# ICEBoard_rev1_1.net
KiCad netlist of a schematic drawn in Altium Designer
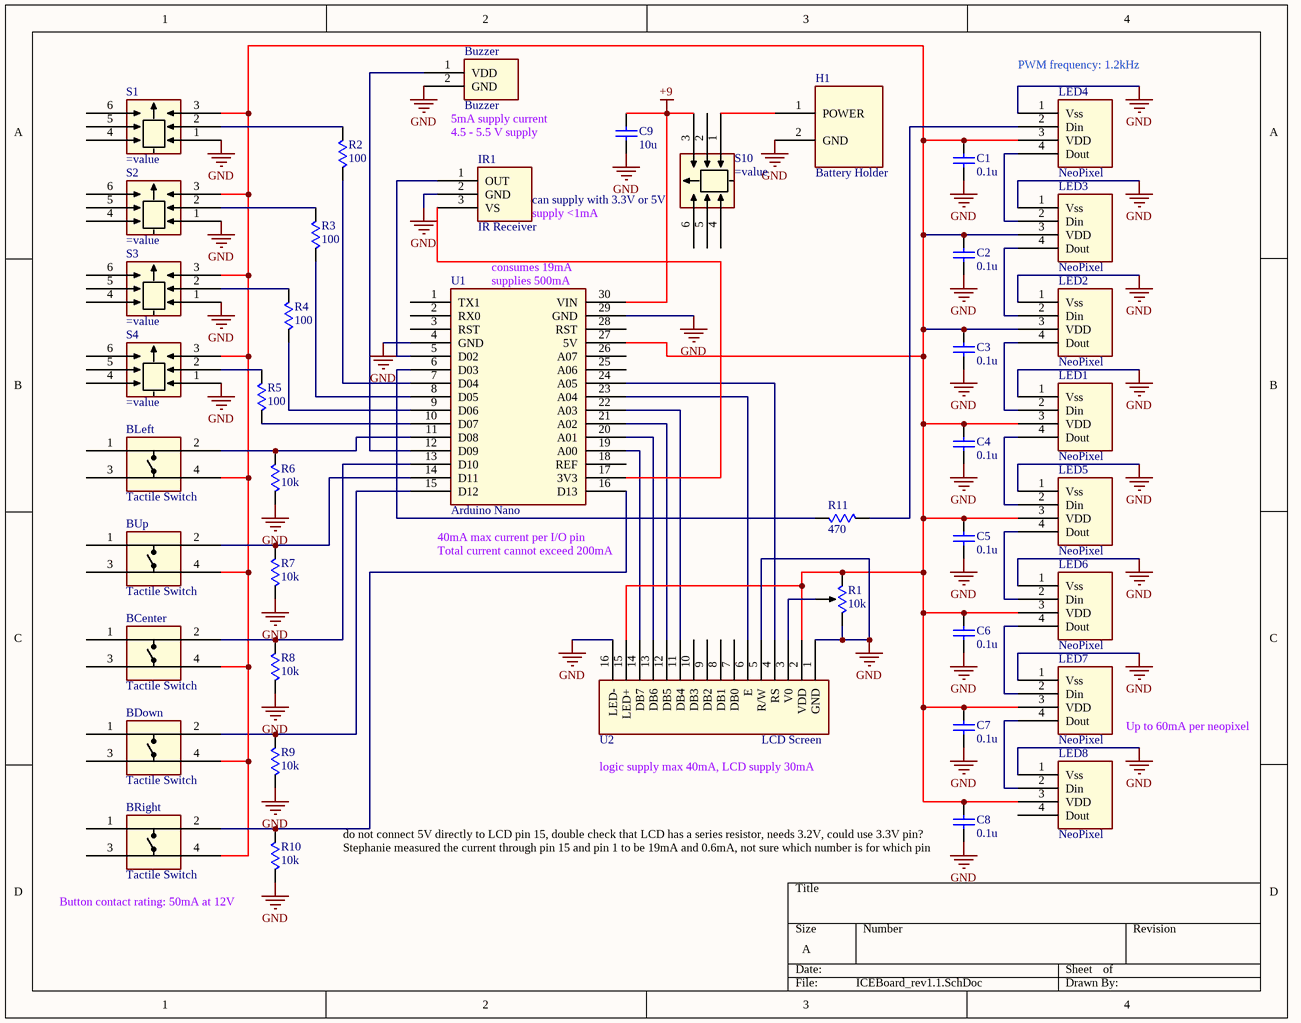
[diagram p0: ICEBoard_rev1.1.SchDoc]

(export (version "E")
  (design (tool "Eeschema 10.0.6"))
  (components
    (comp (ref "BCenter")
      (value "Tactile Switch")
      (footprint "PTS645")
      (libsource (lib "PTS645") (part "PTS645"))
    )
    (comp (ref "BDown")
      (value "Tactile Switch")
      (footprint "PTS645")
      (libsource (lib "PTS645") (part "PTS645"))
    )
    (comp (ref "BLeft")
      (value "Tactile Switch")
      (footprint "PTS645")
      (libsource (lib "PTS645") (part "PTS645"))
    )
    (comp (ref "BRight")
      (value "Tactile Switch")
      (footprint "PTS645")
      (libsource (lib "PTS645") (part "PTS645"))
    )
    (comp (ref "BUp")
      (value "Tactile Switch")
      (footprint "PTS645")
      (libsource (lib "PTS645") (part "PTS645"))
    )
    (comp (ref "Buzzer")
      (value "Buzzer")
      (footprint "TP124005")
      (libsource (lib "TP124005") (part "TP124005"))
    )
    (comp (ref "C1") (value "0.1u") (footprint "Capacitor") (libsource (lib "Capacitor") (part "Capacitor")))
    (comp (ref "C2") (value "0.1u") (footprint "Capacitor") (libsource (lib "Capacitor") (part "Capacitor")))
    (comp (ref "C3") (value "0.1u") (footprint "Capacitor") (libsource (lib "Capacitor") (part "Capacitor")))
    (comp (ref "C4") (value "0.1u") (footprint "Capacitor") (libsource (lib "Capacitor") (part "Capacitor")))
    (comp (ref "C5") (value "0.1u") (footprint "Capacitor") (libsource (lib "Capacitor") (part "Capacitor")))
    (comp (ref "C6") (value "0.1u") (footprint "Capacitor") (libsource (lib "Capacitor") (part "Capacitor")))
    (comp (ref "C7") (value "0.1u") (footprint "Capacitor") (libsource (lib "Capacitor") (part "Capacitor")))
    (comp (ref "C8") (value "0.1u") (footprint "Capacitor") (libsource (lib "Capacitor") (part "Capacitor")))
    (comp (ref "C9")
      (value "10u")
      (footprint "PCBComponent_1")
      (libsource (lib "Capacitor") (part "Capacitor"))
    )
    (comp (ref "H1") (value "Battery Holder") (footprint "BH9VPC") (libsource (lib "BH9VPC") (part "BH9VPC")))
    (comp (ref "IR1")
      (value "IR Receiver")
      (footprint "TSOP382")
      (libsource (lib "TSOP382") (part "TSOP382"))
    )
    (comp (ref "LED1")
      (value "NeoPixel")
      (footprint "NeoPixel")
      (libsource (lib "NeoPixel") (part "NeoPixel"))
    )
    (comp (ref "LED2")
      (value "NeoPixel")
      (footprint "NeoPixel")
      (libsource (lib "NeoPixel") (part "NeoPixel"))
    )
    (comp (ref "LED3")
      (value "NeoPixel")
      (footprint "NeoPixel")
      (libsource (lib "NeoPixel") (part "NeoPixel"))
    )
    (comp (ref "LED4")
      (value "NeoPixel")
      (footprint "NeoPixel")
      (libsource (lib "NeoPixel") (part "NeoPixel"))
    )
    (comp (ref "LED5")
      (value "NeoPixel")
      (footprint "NeoPixel")
      (libsource (lib "NeoPixel") (part "NeoPixel"))
    )
    (comp (ref "LED6")
      (value "NeoPixel")
      (footprint "NeoPixel")
      (libsource (lib "NeoPixel") (part "NeoPixel"))
    )
    (comp (ref "LED7")
      (value "NeoPixel")
      (footprint "NeoPixel")
      (libsource (lib "NeoPixel") (part "NeoPixel"))
    )
    (comp (ref "LED8")
      (value "NeoPixel")
      (footprint "NeoPixel")
      (libsource (lib "NeoPixel") (part "NeoPixel"))
    )
    (comp (ref "R1")
      (value "10k")
      (footprint "TC33X")
      (libsource (lib "Resistor - Variable") (part "Resistor - Variable"))
    )
    (comp (ref "R2") (value "100") (footprint "Resistor1608") (libsource (lib "Resistor") (part "Resistor")))
    (comp (ref "R3") (value "100") (footprint "Resistor1608") (libsource (lib "Resistor") (part "Resistor")))
    (comp (ref "R4") (value "100") (footprint "Resistor1608") (libsource (lib "Resistor") (part "Resistor")))
    (comp (ref "R5") (value "100") (footprint "Resistor1608") (libsource (lib "Resistor") (part "Resistor")))
    (comp (ref "R6") (value "10k") (footprint "Resistor1608") (libsource (lib "Resistor") (part "Resistor")))
    (comp (ref "R7") (value "10k") (footprint "Resistor1608") (libsource (lib "Resistor") (part "Resistor")))
    (comp (ref "R8") (value "10k") (footprint "Resistor1608") (libsource (lib "Resistor") (part "Resistor")))
    (comp (ref "R9") (value "10k") (footprint "Resistor1608") (libsource (lib "Resistor") (part "Resistor")))
    (comp (ref "R10") (value "10k") (footprint "Resistor1608") (libsource (lib "Resistor") (part "Resistor")))
    (comp (ref "R11") (value "470") (footprint "Resistor1608") (libsource (lib "Resistor") (part "Resistor")))
    (comp (ref "S1") (value "~") (footprint "MHSS1104") (libsource (lib "MHSS1104") (part "MHSS1104")))
    (comp (ref "S2") (value "~") (footprint "MHSS1104") (libsource (lib "MHSS1104") (part "MHSS1104")))
    (comp (ref "S3") (value "~") (footprint "MHSS1104") (libsource (lib "MHSS1104") (part "MHSS1104")))
    (comp (ref "S4") (value "~") (footprint "MHSS1104") (libsource (lib "MHSS1104") (part "MHSS1104")))
    (comp (ref "S10") (value "~") (footprint "MHSS1104") (libsource (lib "") (part "MHSS1104_1")))
    (comp (ref "U1")
      (value "Arduino Nano")
      (footprint "ArduinoNano")
      (libsource (lib "ArduinoNano") (part "ArduinoNano"))
    )
    (comp (ref "U2")
      (value "LCD Screen")
      (footprint "TC1602A-01T")
      (libsource (lib "TC1602A-01T") (part "TC1602A-01T"))
    )
  )
  (nets
    (net (code "1") (name "+9") (class "Default")
      (node (ref "C9") (pin "1") (pinfunction "1_1") (pintype "passive"))
      (node (ref "S10") (pin "3") (pintype "passive"))
      (node (ref "U1") (pin "30") (pinfunction "VIN_30") (pintype "passive"))
    )
    (net (code "2") (name "GND") (class "Default")
      (node (ref "Buzzer") (pin "2") (pinfunction "GND_2") (pintype "passive"))
      (node (ref "C1") (pin "2") (pinfunction "2_2") (pintype "passive"))
      (node (ref "C2") (pin "2") (pinfunction "2_2") (pintype "passive"))
      (node (ref "C3") (pin "2") (pinfunction "2_2") (pintype "passive"))
      (node (ref "C4") (pin "2") (pinfunction "2_2") (pintype "passive"))
      (node (ref "C5") (pin "2") (pinfunction "2_2") (pintype "passive"))
      (node (ref "C6") (pin "2") (pinfunction "2_2") (pintype "passive"))
      (node (ref "C7") (pin "2") (pinfunction "2_2") (pintype "passive"))
      (node (ref "C8") (pin "2") (pinfunction "2_2") (pintype "passive"))
      (node (ref "C9") (pin "2") (pinfunction "2_2") (pintype "passive"))
      (node (ref "H1") (pin "2") (pinfunction "GND_2") (pintype "passive"))
      (node (ref "IR1") (pin "2") (pinfunction "GND_2") (pintype "passive"))
      (node (ref "LED1") (pin "1") (pinfunction "Vss_1") (pintype "passive"))
      (node (ref "LED2") (pin "1") (pinfunction "Vss_1") (pintype "passive"))
      (node (ref "LED3") (pin "1") (pinfunction "Vss_1") (pintype "passive"))
      (node (ref "LED4") (pin "1") (pinfunction "Vss_1") (pintype "passive"))
      (node (ref "LED5") (pin "1") (pinfunction "Vss_1") (pintype "passive"))
      (node (ref "LED6") (pin "1") (pinfunction "Vss_1") (pintype "passive"))
      (node (ref "LED7") (pin "1") (pinfunction "Vss_1") (pintype "passive"))
      (node (ref "LED8") (pin "1") (pinfunction "Vss_1") (pintype "passive"))
      (node (ref "R1") (pin "1") (pinfunction "1_1") (pintype "passive"))
      (node (ref "R10") (pin "1") (pinfunction "1_1") (pintype "passive"))
      (node (ref "R6") (pin "1") (pinfunction "1_1") (pintype "passive"))
      (node (ref "R7") (pin "1") (pinfunction "1_1") (pintype "passive"))
      (node (ref "R8") (pin "1") (pinfunction "1_1") (pintype "passive"))
      (node (ref "R9") (pin "1") (pinfunction "1_1") (pintype "passive"))
      (node (ref "S1") (pin "1") (pintype "passive"))
      (node (ref "S2") (pin "1") (pintype "passive"))
      (node (ref "S3") (pin "1") (pintype "passive"))
      (node (ref "S4") (pin "1") (pintype "passive"))
      (node (ref "U1") (pin "29") (pinfunction "GND_29") (pintype "passive"))
      (node (ref "U1") (pin "4") (pinfunction "GND_4") (pintype "passive"))
      (node (ref "U2") (pin "1") (pinfunction "GND_1") (pintype "passive"))
      (node (ref "U2") (pin "16") (pinfunction "LED-_16") (pintype "passive"))
      (node (ref "U2") (pin "5") (pinfunction "R/W_5") (pintype "passive"))
    )
    (net (code "3") (name "Net-(Buzzer-VDD)") (class "Default")
      (node (ref "Buzzer") (pin "1") (pinfunction "VDD_1") (pintype "passive"))
      (node (ref "U1") (pin "12") (pinfunction "D09_12") (pintype "passive"))
    )
    (net (code "4") (name "Net-(H1-POWER)") (class "Default")
      (node (ref "H1") (pin "1") (pinfunction "POWER_1") (pintype "passive"))
      (node (ref "S10") (pin "1") (pintype "passive"))
    )
    (net (code "5") (name "Net-(IR1-OUT)") (class "Default")
      (node (ref "IR1") (pin "1") (pinfunction "OUT_1") (pintype "passive"))
      (node (ref "U1") (pin "5") (pinfunction "D02_5") (pintype "passive"))
    )
    (net (code "6") (name "Net-(IR1-VS)") (class "Default")
      (node (ref "IR1") (pin "3") (pinfunction "VS_3") (pintype "passive"))
      (node (ref "U1") (pin "17") (pinfunction "3V3_17") (pintype "passive"))
    )
    (net (code "7") (name "Net-(LED1-Din)") (class "Default")
      (node (ref "LED1") (pin "2") (pinfunction "Din_2") (pintype "passive"))
      (node (ref "LED2") (pin "4") (pinfunction "Dout_4") (pintype "passive"))
    )
    (net (code "8") (name "Net-(LED1-Dout)") (class "Default")
      (node (ref "LED1") (pin "4") (pinfunction "Dout_4") (pintype "passive"))
      (node (ref "LED5") (pin "2") (pinfunction "Din_2") (pintype "passive"))
    )
    (net (code "9") (name "Net-(LED1-VDD)") (class "Default")
      (node (ref "BCenter") (pin "4") (pintype "passive"))
      (node (ref "BDown") (pin "4") (pintype "passive"))
      (node (ref "BLeft") (pin "4") (pintype "passive"))
      (node (ref "BRight") (pin "4") (pintype "passive"))
      (node (ref "BUp") (pin "4") (pintype "passive"))
      (node (ref "C1") (pin "1") (pinfunction "1_1") (pintype "passive"))
      (node (ref "C2") (pin "1") (pinfunction "1_1") (pintype "passive"))
      (node (ref "C3") (pin "1") (pinfunction "1_1") (pintype "passive"))
      (node (ref "C4") (pin "1") (pinfunction "1_1") (pintype "passive"))
      (node (ref "C5") (pin "1") (pinfunction "1_1") (pintype "passive"))
      (node (ref "C6") (pin "1") (pinfunction "1_1") (pintype "passive"))
      (node (ref "C7") (pin "1") (pinfunction "1_1") (pintype "passive"))
      (node (ref "C8") (pin "1") (pinfunction "1_1") (pintype "passive"))
      (node (ref "LED1") (pin "3") (pinfunction "VDD_3") (pintype "passive"))
      (node (ref "LED2") (pin "3") (pinfunction "VDD_3") (pintype "passive"))
      (node (ref "LED3") (pin "3") (pinfunction "VDD_3") (pintype "passive"))
      (node (ref "LED4") (pin "3") (pinfunction "VDD_3") (pintype "passive"))
      (node (ref "LED5") (pin "3") (pinfunction "VDD_3") (pintype "passive"))
      (node (ref "LED6") (pin "3") (pinfunction "VDD_3") (pintype "passive"))
      (node (ref "LED7") (pin "3") (pinfunction "VDD_3") (pintype "passive"))
      (node (ref "LED8") (pin "3") (pinfunction "VDD_3") (pintype "passive"))
      (node (ref "R1") (pin "3") (pinfunction "3_3") (pintype "passive"))
      (node (ref "S1") (pin "3") (pintype "passive"))
      (node (ref "S2") (pin "3") (pintype "passive"))
      (node (ref "S3") (pin "3") (pintype "passive"))
      (node (ref "S4") (pin "3") (pintype "passive"))
      (node (ref "U1") (pin "27") (pinfunction "5V_27") (pintype "passive"))
      (node (ref "U2") (pin "15") (pinfunction "LED+_15") (pintype "passive"))
      (node (ref "U2") (pin "2") (pinfunction "VDD_2") (pintype "passive"))
    )
    (net (code "10") (name "Net-(LED2-Din)") (class "Default")
      (node (ref "LED2") (pin "2") (pinfunction "Din_2") (pintype "passive"))
      (node (ref "LED3") (pin "4") (pinfunction "Dout_4") (pintype "passive"))
    )
    (net (code "11") (name "Net-(LED3-Din)") (class "Default")
      (node (ref "LED3") (pin "2") (pinfunction "Din_2") (pintype "passive"))
      (node (ref "LED4") (pin "4") (pinfunction "Dout_4") (pintype "passive"))
    )
    (net (code "12") (name "Net-(LED4-Din)") (class "Default")
      (node (ref "LED4") (pin "2") (pinfunction "Din_2") (pintype "passive"))
      (node (ref "R11") (pin "2") (pinfunction "2_2") (pintype "passive"))
    )
    (net (code "13") (name "Net-(LED5-Dout)") (class "Default")
      (node (ref "LED5") (pin "4") (pinfunction "Dout_4") (pintype "passive"))
      (node (ref "LED6") (pin "2") (pinfunction "Din_2") (pintype "passive"))
    )
    (net (code "14") (name "Net-(LED6-Dout)") (class "Default")
      (node (ref "LED6") (pin "4") (pinfunction "Dout_4") (pintype "passive"))
      (node (ref "LED7") (pin "2") (pinfunction "Din_2") (pintype "passive"))
    )
    (net (code "15") (name "Net-(LED7-Dout)") (class "Default")
      (node (ref "LED7") (pin "4") (pinfunction "Dout_4") (pintype "passive"))
      (node (ref "LED8") (pin "2") (pinfunction "Din_2") (pintype "passive"))
    )
    (net (code "16") (name "Net-(R2-Pad2)") (class "Default")
      (node (ref "R2") (pin "2") (pinfunction "2_2") (pintype "passive"))
      (node (ref "S1") (pin "2") (pintype "passive"))
    )
    (net (code "17") (name "Net-(R3-Pad2)") (class "Default")
      (node (ref "R3") (pin "2") (pinfunction "2_2") (pintype "passive"))
      (node (ref "S2") (pin "2") (pintype "passive"))
    )
    (net (code "18") (name "Net-(R4-Pad2)") (class "Default")
      (node (ref "R4") (pin "2") (pinfunction "2_2") (pintype "passive"))
      (node (ref "S3") (pin "2") (pintype "passive"))
    )
    (net (code "19") (name "Net-(R5-Pad2)") (class "Default")
      (node (ref "R5") (pin "2") (pinfunction "2_2") (pintype "passive"))
      (node (ref "S4") (pin "2") (pintype "passive"))
    )
    (net (code "20") (name "Net-(U1-A00)") (class "Default")
      (node (ref "U1") (pin "19") (pinfunction "A00_19") (pintype "passive"))
      (node (ref "U2") (pin "14") (pinfunction "DB7_14") (pintype "passive"))
    )
    (net (code "21") (name "Net-(U1-A01)") (class "Default")
      (node (ref "U1") (pin "20") (pinfunction "A01_20") (pintype "passive"))
      (node (ref "U2") (pin "13") (pinfunction "DB6_13") (pintype "passive"))
    )
    (net (code "22") (name "Net-(U1-A02)") (class "Default")
      (node (ref "U1") (pin "21") (pinfunction "A02_21") (pintype "passive"))
      (node (ref "U2") (pin "12") (pinfunction "DB5_12") (pintype "passive"))
    )
    (net (code "23") (name "Net-(U1-A03)") (class "Default")
      (node (ref "U1") (pin "22") (pinfunction "A03_22") (pintype "passive"))
      (node (ref "U2") (pin "11") (pinfunction "DB4_11") (pintype "passive"))
    )
    (net (code "24") (name "Net-(U1-A04)") (class "Default")
      (node (ref "U1") (pin "23") (pinfunction "A04_23") (pintype "passive"))
      (node (ref "U2") (pin "6") (pinfunction "E_6") (pintype "passive"))
    )
    (net (code "25") (name "Net-(U1-A05)") (class "Default")
      (node (ref "U1") (pin "24") (pinfunction "A05_24") (pintype "passive"))
      (node (ref "U2") (pin "4") (pinfunction "RS_4") (pintype "passive"))
    )
    (net (code "26") (name "Net-(U1-D03)") (class "Default")
      (node (ref "R11") (pin "1") (pinfunction "1_1") (pintype "passive"))
      (node (ref "U1") (pin "6") (pinfunction "D03_6") (pintype "passive"))
    )
    (net (code "27") (name "Net-(U1-D04)") (class "Default")
      (node (ref "R2") (pin "1") (pinfunction "1_1") (pintype "passive"))
      (node (ref "U1") (pin "7") (pinfunction "D04_7") (pintype "passive"))
    )
    (net (code "28") (name "Net-(U1-D05)") (class "Default")
      (node (ref "R3") (pin "1") (pinfunction "1_1") (pintype "passive"))
      (node (ref "U1") (pin "8") (pinfunction "D05_8") (pintype "passive"))
    )
    (net (code "29") (name "Net-(U1-D06)") (class "Default")
      (node (ref "R4") (pin "1") (pinfunction "1_1") (pintype "passive"))
      (node (ref "U1") (pin "9") (pinfunction "D06_9") (pintype "passive"))
    )
    (net (code "30") (name "Net-(U1-D07)") (class "Default")
      (node (ref "R5") (pin "1") (pinfunction "1_1") (pintype "passive"))
      (node (ref "U1") (pin "10") (pinfunction "D07_10") (pintype "passive"))
    )
    (net (code "31") (name "Net-(U1-D08)") (class "Default")
      (node (ref "BLeft") (pin "2") (pintype "passive"))
      (node (ref "R6") (pin "2") (pinfunction "2_2") (pintype "passive"))
      (node (ref "U1") (pin "11") (pinfunction "D08_11") (pintype "passive"))
    )
    (net (code "32") (name "Net-(U1-D10)") (class "Default")
      (node (ref "BCenter") (pin "2") (pintype "passive"))
      (node (ref "R8") (pin "2") (pinfunction "2_2") (pintype "passive"))
      (node (ref "U1") (pin "13") (pinfunction "D10_13") (pintype "passive"))
    )
    (net (code "33") (name "Net-(U1-D11)") (class "Default")
      (node (ref "BUp") (pin "2") (pintype "passive"))
      (node (ref "R7") (pin "2") (pinfunction "2_2") (pintype "passive"))
      (node (ref "U1") (pin "14") (pinfunction "D11_14") (pintype "passive"))
    )
    (net (code "34") (name "Net-(U1-D12)") (class "Default")
      (node (ref "BDown") (pin "2") (pintype "passive"))
      (node (ref "R9") (pin "2") (pinfunction "2_2") (pintype "passive"))
      (node (ref "U1") (pin "15") (pinfunction "D12_15") (pintype "passive"))
    )
    (net (code "35") (name "Net-(U1-D13)") (class "Default")
      (node (ref "BRight") (pin "2") (pintype "passive"))
      (node (ref "R10") (pin "2") (pinfunction "2_2") (pintype "passive"))
      (node (ref "U1") (pin "16") (pinfunction "D13_16") (pintype "passive"))
    )
    (net (code "36") (name "Net-(U2-V0)") (class "Default")
      (node (ref "R1") (pin "2") (pinfunction "2_2") (pintype "passive"))
      (node (ref "U2") (pin "3") (pinfunction "V0_3") (pintype "passive"))
    )
    (net (code "37") (name "unconnected-(BCenter-Pad1)") (class "Default")
      (node (ref "BCenter") (pin "1") (pintype "passive"))
    )
    (net (code "38") (name "unconnected-(BCenter-Pad3)") (class "Default")
      (node (ref "BCenter") (pin "3") (pintype "passive"))
    )
    (net (code "39") (name "unconnected-(BDown-Pad1)") (class "Default")
      (node (ref "BDown") (pin "1") (pintype "passive"))
    )
    (net (code "40") (name "unconnected-(BDown-Pad3)") (class "Default")
      (node (ref "BDown") (pin "3") (pintype "passive"))
    )
    (net (code "41") (name "unconnected-(BLeft-Pad1)") (class "Default")
      (node (ref "BLeft") (pin "1") (pintype "passive"))
    )
    (net (code "42") (name "unconnected-(BLeft-Pad3)") (class "Default")
      (node (ref "BLeft") (pin "3") (pintype "passive"))
    )
    (net (code "43") (name "unconnected-(BRight-Pad1)") (class "Default")
      (node (ref "BRight") (pin "1") (pintype "passive"))
    )
    (net (code "44") (name "unconnected-(BRight-Pad3)") (class "Default")
      (node (ref "BRight") (pin "3") (pintype "passive"))
    )
    (net (code "45") (name "unconnected-(BUp-Pad1)") (class "Default")
      (node (ref "BUp") (pin "1") (pintype "passive"))
    )
    (net (code "46") (name "unconnected-(BUp-Pad3)") (class "Default")
      (node (ref "BUp") (pin "3") (pintype "passive"))
    )
    (net (code "47") (name "unconnected-(LED8-Dout-Pad4)") (class "Default")
      (node (ref "LED8") (pin "4") (pinfunction "Dout_4") (pintype "passive"))
    )
    (net (code "48") (name "unconnected-(S1-Pad4)") (class "Default")
      (node (ref "S1") (pin "4") (pintype "passive"))
    )
    (net (code "49") (name "unconnected-(S1-Pad5)") (class "Default")
      (node (ref "S1") (pin "5") (pintype "passive"))
    )
    (net (code "50") (name "unconnected-(S1-Pad6)") (class "Default")
      (node (ref "S1") (pin "6") (pintype "passive"))
    )
    (net (code "51") (name "unconnected-(S2-Pad4)") (class "Default")
      (node (ref "S2") (pin "4") (pintype "passive"))
    )
    (net (code "52") (name "unconnected-(S2-Pad5)") (class "Default")
      (node (ref "S2") (pin "5") (pintype "passive"))
    )
    (net (code "53") (name "unconnected-(S2-Pad6)") (class "Default")
      (node (ref "S2") (pin "6") (pintype "passive"))
    )
    (net (code "54") (name "unconnected-(S3-Pad4)") (class "Default")
      (node (ref "S3") (pin "4") (pintype "passive"))
    )
    (net (code "55") (name "unconnected-(S3-Pad5)") (class "Default")
      (node (ref "S3") (pin "5") (pintype "passive"))
    )
    (net (code "56") (name "unconnected-(S3-Pad6)") (class "Default")
      (node (ref "S3") (pin "6") (pintype "passive"))
    )
    (net (code "57") (name "unconnected-(S4-Pad4)") (class "Default")
      (node (ref "S4") (pin "4") (pintype "passive"))
    )
    (net (code "58") (name "unconnected-(S4-Pad5)") (class "Default")
      (node (ref "S4") (pin "5") (pintype "passive"))
    )
    (net (code "59") (name "unconnected-(S4-Pad6)") (class "Default")
      (node (ref "S4") (pin "6") (pintype "passive"))
    )
    (net (code "60") (name "unconnected-(S10-Pad2)") (class "Default")
      (node (ref "S10") (pin "2") (pintype "passive"))
    )
    (net (code "61") (name "unconnected-(S10-Pad4)") (class "Default")
      (node (ref "S10") (pin "4") (pintype "passive"))
    )
    (net (code "62") (name "unconnected-(S10-Pad5)") (class "Default")
      (node (ref "S10") (pin "5") (pintype "passive"))
    )
    (net (code "63") (name "unconnected-(S10-Pad6)") (class "Default")
      (node (ref "S10") (pin "6") (pintype "passive"))
    )
    (net (code "64") (name "unconnected-(U1-A06-Pad25)") (class "Default")
      (node (ref "U1") (pin "25") (pinfunction "A06_25") (pintype "passive"))
    )
    (net (code "65") (name "unconnected-(U1-A07-Pad26)") (class "Default")
      (node (ref "U1") (pin "26") (pinfunction "A07_26") (pintype "passive"))
    )
    (net (code "66") (name "unconnected-(U1-REF-Pad18)") (class "Default")
      (node (ref "U1") (pin "18") (pinfunction "REF_18") (pintype "passive"))
    )
    (net (code "67") (name "unconnected-(U1-RST-Pad3)") (class "Default")
      (node (ref "U1") (pin "3") (pinfunction "RST_3") (pintype "passive"))
    )
    (net (code "68") (name "unconnected-(U1-RST-Pad28)") (class "Default")
      (node (ref "U1") (pin "28") (pinfunction "RST_28") (pintype "passive"))
    )
    (net (code "69") (name "unconnected-(U1-RX0-Pad2)") (class "Default")
      (node (ref "U1") (pin "2") (pinfunction "RX0_2") (pintype "passive"))
    )
    (net (code "70") (name "unconnected-(U1-TX1-Pad1)") (class "Default")
      (node (ref "U1") (pin "1") (pinfunction "TX1_1") (pintype "passive"))
    )
    (net (code "71") (name "unconnected-(U2-DB0-Pad7)") (class "Default")
      (node (ref "U2") (pin "7") (pinfunction "DB0_7") (pintype "passive"))
    )
    (net (code "72") (name "unconnected-(U2-DB1-Pad8)") (class "Default")
      (node (ref "U2") (pin "8") (pinfunction "DB1_8") (pintype "passive"))
    )
    (net (code "73") (name "unconnected-(U2-DB2-Pad9)") (class "Default")
      (node (ref "U2") (pin "9") (pinfunction "DB2_9") (pintype "passive"))
    )
    (net (code "74") (name "unconnected-(U2-DB3-Pad10)") (class "Default")
      (node (ref "U2") (pin "10") (pinfunction "DB3_10") (pintype "passive"))
    )
  )
)
